# sch3.net
KiCad netlist of a schematic drawn in EAGLE
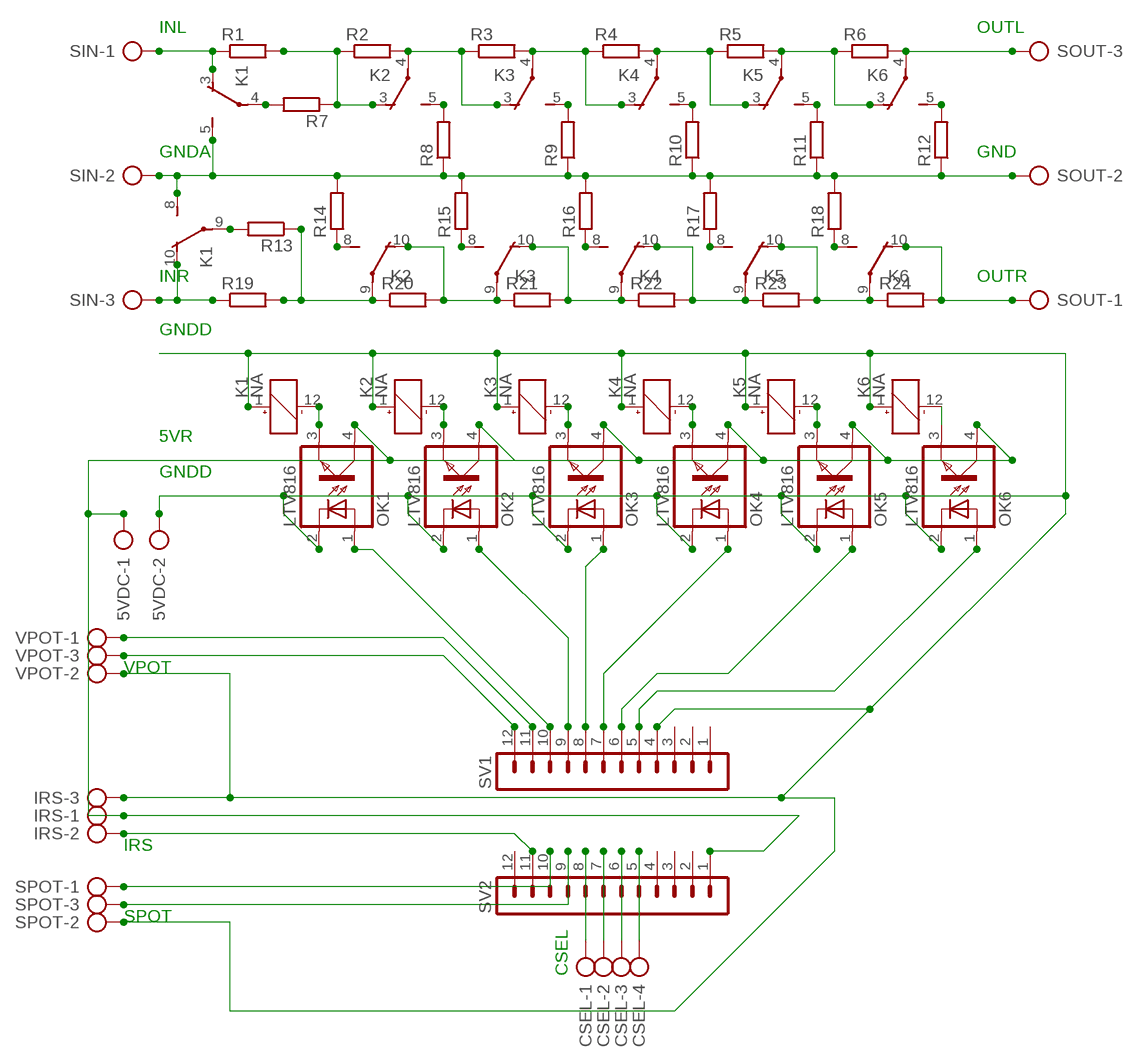
[diagram p0: schematic, sheet 1]

(export (version "E")
  (design (tool "Eeschema 10.0.6"))
  (components
    (comp (ref "5VDC")
      (value "AK500/2")
      (footprint "eagle-import:AK500_2")
      (libsource (lib "eagle-import") (part "AK500/2"))
    )
    (comp (ref "CSEL")
      (value "AK500/4")
      (footprint "eagle-import:AK500_4")
      (libsource (lib "eagle-import") (part "AK500/4"))
    )
    (comp (ref "IRS")
      (value "AK500/3")
      (footprint "eagle-import:AK500_3")
      (libsource (lib "eagle-import") (part "AK500/3"))
    )
    (comp (ref "K1") (value "NA") (footprint "eagle-import:NA") (libsource (lib "eagle-import") (part "NA")))
    (comp (ref "K2") (value "NA") (footprint "eagle-import:NA") (libsource (lib "eagle-import") (part "NA")))
    (comp (ref "K3") (value "NA") (footprint "eagle-import:NA") (libsource (lib "eagle-import") (part "NA")))
    (comp (ref "K4") (value "NA") (footprint "eagle-import:NA") (libsource (lib "eagle-import") (part "NA")))
    (comp (ref "K5") (value "NA") (footprint "eagle-import:NA") (libsource (lib "eagle-import") (part "NA")))
    (comp (ref "K6") (value "NA") (footprint "eagle-import:NA") (libsource (lib "eagle-import") (part "NA")))
    (comp (ref "OK1")
      (value "LTV816")
      (footprint "eagle-import:DIL04")
      (libsource (lib "eagle-import") (part "LTV816"))
    )
    (comp (ref "OK2")
      (value "LTV816")
      (footprint "eagle-import:DIL04")
      (libsource (lib "eagle-import") (part "LTV816"))
    )
    (comp (ref "OK3")
      (value "LTV816")
      (footprint "eagle-import:DIL04")
      (libsource (lib "eagle-import") (part "LTV816"))
    )
    (comp (ref "OK4")
      (value "LTV816")
      (footprint "eagle-import:DIL04")
      (libsource (lib "eagle-import") (part "LTV816"))
    )
    (comp (ref "OK5")
      (value "LTV816")
      (footprint "eagle-import:DIL04")
      (libsource (lib "eagle-import") (part "LTV816"))
    )
    (comp (ref "OK6")
      (value "LTV816")
      (footprint "eagle-import:DIL04")
      (libsource (lib "eagle-import") (part "LTV816"))
    )
    (comp (ref "R1")
      (value "R-EU_0204/7")
      (footprint "eagle-import:0204_7")
      (libsource (lib "eagle-import") (part "R-EU_0204/7"))
    )
    (comp (ref "R2")
      (value "R-EU_0204/7")
      (footprint "eagle-import:0204_7")
      (libsource (lib "eagle-import") (part "R-EU_0204/7"))
    )
    (comp (ref "R3")
      (value "R-EU_0204/7")
      (footprint "eagle-import:0204_7")
      (libsource (lib "eagle-import") (part "R-EU_0204/7"))
    )
    (comp (ref "R4")
      (value "R-EU_0204/7")
      (footprint "eagle-import:0204_7")
      (libsource (lib "eagle-import") (part "R-EU_0204/7"))
    )
    (comp (ref "R5")
      (value "R-EU_0204/7")
      (footprint "eagle-import:0204_7")
      (libsource (lib "eagle-import") (part "R-EU_0204/7"))
    )
    (comp (ref "R6")
      (value "R-EU_0204/7")
      (footprint "eagle-import:0204_7")
      (libsource (lib "eagle-import") (part "R-EU_0204/7"))
    )
    (comp (ref "R7")
      (value "R-EU_0204/7")
      (footprint "eagle-import:0204_7")
      (libsource (lib "eagle-import") (part "R-EU_0204/7"))
    )
    (comp (ref "R8")
      (value "R-EU_0204/7")
      (footprint "eagle-import:0204_7")
      (libsource (lib "eagle-import") (part "R-EU_0204/7"))
    )
    (comp (ref "R9")
      (value "R-EU_0204/7")
      (footprint "eagle-import:0204_7")
      (libsource (lib "eagle-import") (part "R-EU_0204/7"))
    )
    (comp (ref "R10")
      (value "R-EU_0204/7")
      (footprint "eagle-import:0204_7")
      (libsource (lib "eagle-import") (part "R-EU_0204/7"))
    )
    (comp (ref "R11")
      (value "R-EU_0204/7")
      (footprint "eagle-import:0204_7")
      (libsource (lib "eagle-import") (part "R-EU_0204/7"))
    )
    (comp (ref "R12")
      (value "R-EU_0204/7")
      (footprint "eagle-import:0204_7")
      (libsource (lib "eagle-import") (part "R-EU_0204/7"))
    )
    (comp (ref "R13")
      (value "R-EU_0204/7")
      (footprint "eagle-import:0204_7")
      (libsource (lib "eagle-import") (part "R-EU_0204/7"))
    )
    (comp (ref "R14")
      (value "R-EU_0204/7")
      (footprint "eagle-import:0204_7")
      (libsource (lib "eagle-import") (part "R-EU_0204/7"))
    )
    (comp (ref "R15")
      (value "R-EU_0204/7")
      (footprint "eagle-import:0204_7")
      (libsource (lib "eagle-import") (part "R-EU_0204/7"))
    )
    (comp (ref "R16")
      (value "R-EU_0204/7")
      (footprint "eagle-import:0204_7")
      (libsource (lib "eagle-import") (part "R-EU_0204/7"))
    )
    (comp (ref "R17")
      (value "R-EU_0204/7")
      (footprint "eagle-import:0204_7")
      (libsource (lib "eagle-import") (part "R-EU_0204/7"))
    )
    (comp (ref "R18")
      (value "R-EU_0204/7")
      (footprint "eagle-import:0204_7")
      (libsource (lib "eagle-import") (part "R-EU_0204/7"))
    )
    (comp (ref "R19")
      (value "R-EU_0204/7")
      (footprint "eagle-import:0204_7")
      (libsource (lib "eagle-import") (part "R-EU_0204/7"))
    )
    (comp (ref "R20")
      (value "R-EU_0204/7")
      (footprint "eagle-import:0204_7")
      (libsource (lib "eagle-import") (part "R-EU_0204/7"))
    )
    (comp (ref "R21")
      (value "R-EU_0204/7")
      (footprint "eagle-import:0204_7")
      (libsource (lib "eagle-import") (part "R-EU_0204/7"))
    )
    (comp (ref "R22")
      (value "R-EU_0204/7")
      (footprint "eagle-import:0204_7")
      (libsource (lib "eagle-import") (part "R-EU_0204/7"))
    )
    (comp (ref "R23")
      (value "R-EU_0204/7")
      (footprint "eagle-import:0204_7")
      (libsource (lib "eagle-import") (part "R-EU_0204/7"))
    )
    (comp (ref "R24")
      (value "R-EU_0204/7")
      (footprint "eagle-import:0204_7")
      (libsource (lib "eagle-import") (part "R-EU_0204/7"))
    )
    (comp (ref "SIN")
      (value "AK500/3")
      (footprint "eagle-import:AK500_3")
      (libsource (lib "eagle-import") (part "AK500/3"))
    )
    (comp (ref "SOUT")
      (value "AK500/3")
      (footprint "eagle-import:AK500_3")
      (libsource (lib "eagle-import") (part "AK500/3"))
    )
    (comp (ref "SPOT")
      (value "AK500/3")
      (footprint "eagle-import:AK500_3")
      (libsource (lib "eagle-import") (part "AK500/3"))
    )
    (comp (ref "SV1")
      (value "MA12-1")
      (footprint "eagle-import:MA12-1")
      (libsource (lib "eagle-import") (part "MA12-1"))
    )
    (comp (ref "SV2")
      (value "MA12-1")
      (footprint "eagle-import:MA12-1")
      (libsource (lib "eagle-import") (part "MA12-1"))
    )
    (comp (ref "VPOT")
      (value "AK500/3")
      (footprint "eagle-import:AK500_3")
      (libsource (lib "eagle-import") (part "AK500/3"))
    )
  )
  (nets
    (net (code "1") (name "Net-(5VDCA-KL)") (class "Default")
      (node (ref "5VDC") (pin "1") (pinfunction "KL_1") (pintype "passive"))
      (node (ref "IRS") (pin "1") (pinfunction "KL_1") (pintype "passive"))
      (node (ref "OK1") (pin "4") (pinfunction "COL_4") (pintype "passive"))
      (node (ref "OK2") (pin "4") (pinfunction "COL_4") (pintype "passive"))
      (node (ref "OK3") (pin "4") (pinfunction "COL_4") (pintype "passive"))
      (node (ref "OK4") (pin "4") (pinfunction "COL_4") (pintype "passive"))
      (node (ref "OK5") (pin "4") (pinfunction "COL_4") (pintype "passive"))
      (node (ref "OK6") (pin "4") (pinfunction "COL_4") (pintype "passive"))
      (node (ref "SV2") (pin "1") (pinfunction "1_1") (pintype "passive"))
    )
    (net (code "2") (name "Net-(5VDCB-KL)") (class "Default")
      (node (ref "5VDC") (pin "2") (pinfunction "KL_2") (pintype "passive"))
      (node (ref "IRS") (pin "3") (pinfunction "KL_3") (pintype "passive"))
      (node (ref "K1") (pin "1") (pinfunction "+_1") (pintype "passive"))
      (node (ref "K2") (pin "1") (pinfunction "+_1") (pintype "passive"))
      (node (ref "K3") (pin "1") (pinfunction "+_1") (pintype "passive"))
      (node (ref "K4") (pin "1") (pinfunction "+_1") (pintype "passive"))
      (node (ref "K5") (pin "1") (pinfunction "+_1") (pintype "passive"))
      (node (ref "K6") (pin "1") (pinfunction "+_1") (pintype "passive"))
      (node (ref "OK1") (pin "2") (pinfunction "C_2") (pintype "passive"))
      (node (ref "OK2") (pin "2") (pinfunction "C_2") (pintype "passive"))
      (node (ref "OK3") (pin "2") (pinfunction "C_2") (pintype "passive"))
      (node (ref "OK4") (pin "2") (pinfunction "C_2") (pintype "passive"))
      (node (ref "OK5") (pin "2") (pinfunction "C_2") (pintype "passive"))
      (node (ref "OK6") (pin "2") (pinfunction "C_2") (pintype "passive"))
      (node (ref "SPOT") (pin "2") (pinfunction "KL_2") (pintype "passive"))
      (node (ref "SV1") (pin "4") (pinfunction "4_4") (pintype "passive"))
      (node (ref "VPOT") (pin "2") (pinfunction "KL_2") (pintype "passive"))
    )
    (net (code "3") (name "Net-(CSELA-KL)") (class "Default")
      (node (ref "CSEL") (pin "1") (pinfunction "KL_1") (pintype "passive"))
      (node (ref "SV2") (pin "8") (pinfunction "8_8") (pintype "passive"))
    )
    (net (code "4") (name "Net-(CSELB-KL)") (class "Default")
      (node (ref "CSEL") (pin "2") (pinfunction "KL_2") (pintype "passive"))
      (node (ref "SV2") (pin "7") (pinfunction "7_7") (pintype "passive"))
    )
    (net (code "5") (name "Net-(CSELC-KL)") (class "Default")
      (node (ref "CSEL") (pin "3") (pinfunction "KL_3") (pintype "passive"))
      (node (ref "SV2") (pin "6") (pinfunction "6_6") (pintype "passive"))
    )
    (net (code "6") (name "Net-(CSELD-KL)") (class "Default")
      (node (ref "CSEL") (pin "4") (pinfunction "KL_4") (pintype "passive"))
      (node (ref "SV2") (pin "5") (pinfunction "5_5") (pintype "passive"))
    )
    (net (code "7") (name "Net-(IRSB-KL)") (class "Default")
      (node (ref "IRS") (pin "2") (pinfunction "KL_2") (pintype "passive"))
      (node (ref "SV2") (pin "11") (pinfunction "11_11") (pintype "passive"))
    )
    (net (code "8") (name "Net-(K1A--)") (class "Default")
      (node (ref "K1") (pin "12") (pinfunction "-_12") (pintype "passive"))
      (node (ref "OK1") (pin "3") (pinfunction "EMIT_3") (pintype "passive"))
    )
    (net (code "9") (name "Net-(K1B-O)") (class "Default")
      (node (ref "K1") (pin "3") (pinfunction "O_3") (pintype "passive"))
      (node (ref "R1") (pin "1") (pinfunction "1_1") (pintype "passive"))
      (node (ref "SIN") (pin "1") (pinfunction "KL_1") (pintype "passive"))
    )
    (net (code "10") (name "Net-(K1B-P)") (class "Default")
      (node (ref "K1") (pin "4") (pinfunction "P_4") (pintype "passive"))
      (node (ref "R7") (pin "2") (pinfunction "2_2") (pintype "passive"))
    )
    (net (code "11") (name "Net-(K1B-S)") (class "Default")
      (node (ref "K1") (pin "5") (pinfunction "S_5") (pintype "passive"))
      (node (ref "K1") (pin "8") (pinfunction "S_8") (pintype "passive"))
      (node (ref "R10") (pin "1") (pinfunction "1_1") (pintype "passive"))
      (node (ref "R11") (pin "1") (pinfunction "1_1") (pintype "passive"))
      (node (ref "R12") (pin "1") (pinfunction "1_1") (pintype "passive"))
      (node (ref "R14") (pin "2") (pinfunction "2_2") (pintype "passive"))
      (node (ref "R15") (pin "2") (pinfunction "2_2") (pintype "passive"))
      (node (ref "R16") (pin "2") (pinfunction "2_2") (pintype "passive"))
      (node (ref "R17") (pin "2") (pinfunction "2_2") (pintype "passive"))
      (node (ref "R18") (pin "2") (pinfunction "2_2") (pintype "passive"))
      (node (ref "R8") (pin "1") (pinfunction "1_1") (pintype "passive"))
      (node (ref "R9") (pin "1") (pinfunction "1_1") (pintype "passive"))
      (node (ref "SIN") (pin "2") (pinfunction "KL_2") (pintype "passive"))
      (node (ref "SOUT") (pin "2") (pinfunction "KL_2") (pintype "passive"))
    )
    (net (code "12") (name "Net-(K1C-O)") (class "Default")
      (node (ref "K1") (pin "10") (pinfunction "O_10") (pintype "passive"))
      (node (ref "R19") (pin "1") (pinfunction "1_1") (pintype "passive"))
      (node (ref "SIN") (pin "3") (pinfunction "KL_3") (pintype "passive"))
    )
    (net (code "13") (name "Net-(K1C-P)") (class "Default")
      (node (ref "K1") (pin "9") (pinfunction "P_9") (pintype "passive"))
      (node (ref "R13") (pin "2") (pinfunction "2_2") (pintype "passive"))
    )
    (net (code "14") (name "Net-(K2A--)") (class "Default")
      (node (ref "K2") (pin "12") (pinfunction "-_12") (pintype "passive"))
      (node (ref "OK2") (pin "3") (pinfunction "EMIT_3") (pintype "passive"))
    )
    (net (code "15") (name "Net-(K2B-O)") (class "Default")
      (node (ref "K2") (pin "3") (pinfunction "O_3") (pintype "passive"))
      (node (ref "R1") (pin "2") (pinfunction "2_2") (pintype "passive"))
      (node (ref "R2") (pin "1") (pinfunction "1_1") (pintype "passive"))
      (node (ref "R7") (pin "1") (pinfunction "1_1") (pintype "passive"))
    )
    (net (code "16") (name "Net-(K2B-P)") (class "Default")
      (node (ref "K2") (pin "4") (pinfunction "P_4") (pintype "passive"))
      (node (ref "K3") (pin "3") (pinfunction "O_3") (pintype "passive"))
      (node (ref "R2") (pin "2") (pinfunction "2_2") (pintype "passive"))
      (node (ref "R3") (pin "1") (pinfunction "1_1") (pintype "passive"))
    )
    (net (code "17") (name "Net-(K2B-S)") (class "Default")
      (node (ref "K2") (pin "5") (pinfunction "S_5") (pintype "passive"))
      (node (ref "R8") (pin "2") (pinfunction "2_2") (pintype "passive"))
    )
    (net (code "18") (name "Net-(K2C-O)") (class "Default")
      (node (ref "K2") (pin "10") (pinfunction "O_10") (pintype "passive"))
      (node (ref "K3") (pin "9") (pinfunction "P_9") (pintype "passive"))
      (node (ref "R20") (pin "2") (pinfunction "2_2") (pintype "passive"))
      (node (ref "R21") (pin "1") (pinfunction "1_1") (pintype "passive"))
    )
    (net (code "19") (name "Net-(K2C-P)") (class "Default")
      (node (ref "K2") (pin "9") (pinfunction "P_9") (pintype "passive"))
      (node (ref "R13") (pin "1") (pinfunction "1_1") (pintype "passive"))
      (node (ref "R19") (pin "2") (pinfunction "2_2") (pintype "passive"))
      (node (ref "R20") (pin "1") (pinfunction "1_1") (pintype "passive"))
    )
    (net (code "20") (name "Net-(K2C-S)") (class "Default")
      (node (ref "K2") (pin "8") (pinfunction "S_8") (pintype "passive"))
      (node (ref "R14") (pin "1") (pinfunction "1_1") (pintype "passive"))
    )
    (net (code "21") (name "Net-(K3A--)") (class "Default")
      (node (ref "K3") (pin "12") (pinfunction "-_12") (pintype "passive"))
      (node (ref "OK3") (pin "3") (pinfunction "EMIT_3") (pintype "passive"))
    )
    (net (code "22") (name "Net-(K3B-P)") (class "Default")
      (node (ref "K3") (pin "4") (pinfunction "P_4") (pintype "passive"))
      (node (ref "K4") (pin "3") (pinfunction "O_3") (pintype "passive"))
      (node (ref "R3") (pin "2") (pinfunction "2_2") (pintype "passive"))
      (node (ref "R4") (pin "1") (pinfunction "1_1") (pintype "passive"))
    )
    (net (code "23") (name "Net-(K3B-S)") (class "Default")
      (node (ref "K3") (pin "5") (pinfunction "S_5") (pintype "passive"))
      (node (ref "R9") (pin "2") (pinfunction "2_2") (pintype "passive"))
    )
    (net (code "24") (name "Net-(K3C-O)") (class "Default")
      (node (ref "K3") (pin "10") (pinfunction "O_10") (pintype "passive"))
      (node (ref "K4") (pin "9") (pinfunction "P_9") (pintype "passive"))
      (node (ref "R21") (pin "2") (pinfunction "2_2") (pintype "passive"))
      (node (ref "R22") (pin "1") (pinfunction "1_1") (pintype "passive"))
    )
    (net (code "25") (name "Net-(K3C-S)") (class "Default")
      (node (ref "K3") (pin "8") (pinfunction "S_8") (pintype "passive"))
      (node (ref "R15") (pin "1") (pinfunction "1_1") (pintype "passive"))
    )
    (net (code "26") (name "Net-(K4A--)") (class "Default")
      (node (ref "K4") (pin "12") (pinfunction "-_12") (pintype "passive"))
      (node (ref "OK4") (pin "3") (pinfunction "EMIT_3") (pintype "passive"))
    )
    (net (code "27") (name "Net-(K4B-P)") (class "Default")
      (node (ref "K4") (pin "4") (pinfunction "P_4") (pintype "passive"))
      (node (ref "K5") (pin "3") (pinfunction "O_3") (pintype "passive"))
      (node (ref "R4") (pin "2") (pinfunction "2_2") (pintype "passive"))
      (node (ref "R5") (pin "1") (pinfunction "1_1") (pintype "passive"))
    )
    (net (code "28") (name "Net-(K4B-S)") (class "Default")
      (node (ref "K4") (pin "5") (pinfunction "S_5") (pintype "passive"))
      (node (ref "R10") (pin "2") (pinfunction "2_2") (pintype "passive"))
    )
    (net (code "29") (name "Net-(K4C-O)") (class "Default")
      (node (ref "K4") (pin "10") (pinfunction "O_10") (pintype "passive"))
      (node (ref "K5") (pin "9") (pinfunction "P_9") (pintype "passive"))
      (node (ref "R22") (pin "2") (pinfunction "2_2") (pintype "passive"))
      (node (ref "R23") (pin "1") (pinfunction "1_1") (pintype "passive"))
    )
    (net (code "30") (name "Net-(K4C-S)") (class "Default")
      (node (ref "K4") (pin "8") (pinfunction "S_8") (pintype "passive"))
      (node (ref "R16") (pin "1") (pinfunction "1_1") (pintype "passive"))
    )
    (net (code "31") (name "Net-(K5A--)") (class "Default")
      (node (ref "K5") (pin "12") (pinfunction "-_12") (pintype "passive"))
      (node (ref "OK5") (pin "3") (pinfunction "EMIT_3") (pintype "passive"))
    )
    (net (code "32") (name "Net-(K5B-P)") (class "Default")
      (node (ref "K5") (pin "4") (pinfunction "P_4") (pintype "passive"))
      (node (ref "K6") (pin "3") (pinfunction "O_3") (pintype "passive"))
      (node (ref "R5") (pin "2") (pinfunction "2_2") (pintype "passive"))
      (node (ref "R6") (pin "1") (pinfunction "1_1") (pintype "passive"))
    )
    (net (code "33") (name "Net-(K5B-S)") (class "Default")
      (node (ref "K5") (pin "5") (pinfunction "S_5") (pintype "passive"))
      (node (ref "R11") (pin "2") (pinfunction "2_2") (pintype "passive"))
    )
    (net (code "34") (name "Net-(K5C-O)") (class "Default")
      (node (ref "K5") (pin "10") (pinfunction "O_10") (pintype "passive"))
      (node (ref "K6") (pin "9") (pinfunction "P_9") (pintype "passive"))
      (node (ref "R23") (pin "2") (pinfunction "2_2") (pintype "passive"))
      (node (ref "R24") (pin "1") (pinfunction "1_1") (pintype "passive"))
    )
    (net (code "35") (name "Net-(K5C-S)") (class "Default")
      (node (ref "K5") (pin "8") (pinfunction "S_8") (pintype "passive"))
      (node (ref "R17") (pin "1") (pinfunction "1_1") (pintype "passive"))
    )
    (net (code "36") (name "Net-(K6A--)") (class "Default")
      (node (ref "K6") (pin "12") (pinfunction "-_12") (pintype "passive"))
      (node (ref "OK6") (pin "3") (pinfunction "EMIT_3") (pintype "passive"))
    )
    (net (code "37") (name "Net-(K6B-P)") (class "Default")
      (node (ref "K6") (pin "4") (pinfunction "P_4") (pintype "passive"))
      (node (ref "R6") (pin "2") (pinfunction "2_2") (pintype "passive"))
      (node (ref "SOUT") (pin "3") (pinfunction "KL_3") (pintype "passive"))
    )
    (net (code "38") (name "Net-(K6B-S)") (class "Default")
      (node (ref "K6") (pin "5") (pinfunction "S_5") (pintype "passive"))
      (node (ref "R12") (pin "2") (pinfunction "2_2") (pintype "passive"))
    )
    (net (code "39") (name "Net-(K6C-O)") (class "Default")
      (node (ref "K6") (pin "10") (pinfunction "O_10") (pintype "passive"))
      (node (ref "R24") (pin "2") (pinfunction "2_2") (pintype "passive"))
      (node (ref "SOUT") (pin "1") (pinfunction "KL_1") (pintype "passive"))
    )
    (net (code "40") (name "Net-(K6C-S)") (class "Default")
      (node (ref "K6") (pin "8") (pinfunction "S_8") (pintype "passive"))
      (node (ref "R18") (pin "1") (pinfunction "1_1") (pintype "passive"))
    )
    (net (code "41") (name "Net-(OK1-A)") (class "Default")
      (node (ref "OK1") (pin "1") (pinfunction "A_1") (pintype "passive"))
      (node (ref "SV1") (pin "10") (pinfunction "10_10") (pintype "passive"))
    )
    (net (code "42") (name "Net-(OK2-A)") (class "Default")
      (node (ref "OK2") (pin "1") (pinfunction "A_1") (pintype "passive"))
      (node (ref "SV1") (pin "9") (pinfunction "9_9") (pintype "passive"))
    )
    (net (code "43") (name "Net-(OK3-A)") (class "Default")
      (node (ref "OK3") (pin "1") (pinfunction "A_1") (pintype "passive"))
      (node (ref "SV1") (pin "8") (pinfunction "8_8") (pintype "passive"))
    )
    (net (code "44") (name "Net-(OK4-A)") (class "Default")
      (node (ref "OK4") (pin "1") (pinfunction "A_1") (pintype "passive"))
      (node (ref "SV1") (pin "7") (pinfunction "7_7") (pintype "passive"))
    )
    (net (code "45") (name "Net-(OK5-A)") (class "Default")
      (node (ref "OK5") (pin "1") (pinfunction "A_1") (pintype "passive"))
      (node (ref "SV1") (pin "6") (pinfunction "6_6") (pintype "passive"))
    )
    (net (code "46") (name "Net-(OK6-A)") (class "Default")
      (node (ref "OK6") (pin "1") (pinfunction "A_1") (pintype "passive"))
      (node (ref "SV1") (pin "5") (pinfunction "5_5") (pintype "passive"))
    )
    (net (code "47") (name "Net-(SPOTA-KL)") (class "Default")
      (node (ref "SPOT") (pin "1") (pinfunction "KL_1") (pintype "passive"))
      (node (ref "SV2") (pin "10") (pinfunction "10_10") (pintype "passive"))
    )
    (net (code "48") (name "Net-(SPOTC-KL)") (class "Default")
      (node (ref "SPOT") (pin "3") (pinfunction "KL_3") (pintype "passive"))
      (node (ref "SV2") (pin "9") (pinfunction "9_9") (pintype "passive"))
    )
    (net (code "49") (name "Net-(VPOTA-KL)") (class "Default")
      (node (ref "SV1") (pin "11") (pinfunction "11_11") (pintype "passive"))
      (node (ref "VPOT") (pin "1") (pinfunction "KL_1") (pintype "passive"))
    )
    (net (code "50") (name "Net-(VPOTC-KL)") (class "Default")
      (node (ref "SV1") (pin "12") (pinfunction "12_12") (pintype "passive"))
      (node (ref "VPOT") (pin "3") (pinfunction "KL_3") (pintype "passive"))
    )
    (net (code "51") (name "unconnected-(SV1-Pad1)") (class "Default")
      (node (ref "SV1") (pin "1") (pinfunction "1_1") (pintype "passive"))
    )
    (net (code "52") (name "unconnected-(SV1-Pad2)") (class "Default")
      (node (ref "SV1") (pin "2") (pinfunction "2_2") (pintype "passive"))
    )
    (net (code "53") (name "unconnected-(SV1-Pad3)") (class "Default")
      (node (ref "SV1") (pin "3") (pinfunction "3_3") (pintype "passive"))
    )
    (net (code "54") (name "unconnected-(SV2-Pad2)") (class "Default")
      (node (ref "SV2") (pin "2") (pinfunction "2_2") (pintype "passive"))
    )
    (net (code "55") (name "unconnected-(SV2-Pad3)") (class "Default")
      (node (ref "SV2") (pin "3") (pinfunction "3_3") (pintype "passive"))
    )
    (net (code "56") (name "unconnected-(SV2-Pad4)") (class "Default")
      (node (ref "SV2") (pin "4") (pinfunction "4_4") (pintype "passive"))
    )
    (net (code "57") (name "unconnected-(SV2-Pad12)") (class "Default")
      (node (ref "SV2") (pin "12") (pinfunction "12_12") (pintype "passive"))
    )
  )
)
